# stm32_nrf.net
KiCad netlist of a schematic drawn in EAGLE
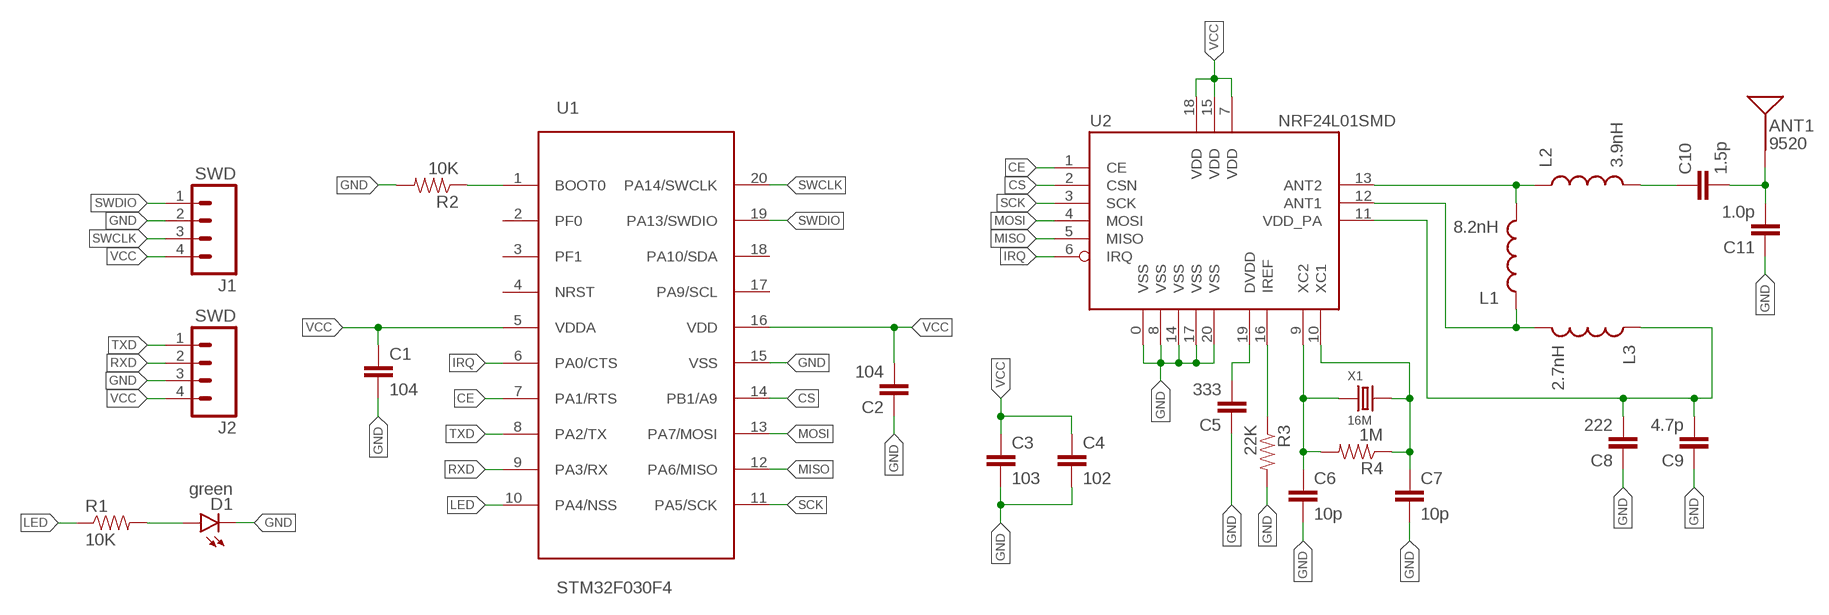
[diagram p0: schematic, sheet 1]

(export (version "E")
  (design (tool "Eeschema 10.0.6"))
  (components
    (comp (ref "ANT1")
      (value "9520")
      (footprint "eagle-import:ANT-2.4GHZ-9.5X2.0MM")
      (libsource (lib "eagle-import") (part "ANTENNA2.4GHZ-9.5X2.0MM"))
    )
    (comp (ref "C1")
      (value "104")
      (footprint "eagle-import:0402-CAP")
      (libsource (lib "eagle-import") (part "CAP0402-CAP"))
    )
    (comp (ref "C2")
      (value "104")
      (footprint "eagle-import:0402-CAP")
      (libsource (lib "eagle-import") (part "CAP0402-CAP"))
    )
    (comp (ref "C3")
      (value "103")
      (footprint "eagle-import:0402-CAP")
      (libsource (lib "eagle-import") (part "CAP0402-CAP"))
    )
    (comp (ref "C4")
      (value "102")
      (footprint "eagle-import:0402-CAP")
      (libsource (lib "eagle-import") (part "CAP0402-CAP"))
    )
    (comp (ref "C5")
      (value "333")
      (footprint "eagle-import:0402-CAP")
      (libsource (lib "eagle-import") (part "CAP0402-CAP"))
    )
    (comp (ref "C6")
      (value "10p")
      (footprint "eagle-import:0402-CAP")
      (libsource (lib "eagle-import") (part "CAP0402-CAP"))
    )
    (comp (ref "C7")
      (value "10p")
      (footprint "eagle-import:0402-CAP")
      (libsource (lib "eagle-import") (part "CAP0402-CAP"))
    )
    (comp (ref "C8")
      (value "222")
      (footprint "eagle-import:0402-CAP")
      (libsource (lib "eagle-import") (part "CAP0402-CAP"))
    )
    (comp (ref "C9")
      (value "4.7p")
      (footprint "eagle-import:0402-CAP")
      (libsource (lib "eagle-import") (part "CAP0402-CAP"))
    )
    (comp (ref "C10")
      (value "1.5p")
      (footprint "eagle-import:0402-CAP")
      (libsource (lib "eagle-import") (part "CAP0402-CAP"))
    )
    (comp (ref "C11")
      (value "1.0p")
      (footprint "eagle-import:0402-CAP")
      (libsource (lib "eagle-import") (part "CAP0402-CAP"))
    )
    (comp (ref "D1")
      (value "green")
      (footprint "eagle-import:LED-0603-EASY")
      (libsource (lib "eagle-import") (part "LED-EASY"))
    )
    (comp (ref "J1")
      (value "SWD")
      (footprint "eagle-import:1X04_NO_SILK")
      (libsource (lib "eagle-import") (part "M041X04_NO_SILK"))
    )
    (comp (ref "J2")
      (value "SWD")
      (footprint "eagle-import:1X04_NO_SILK")
      (libsource (lib "eagle-import") (part "M041X04_NO_SILK"))
    )
    (comp (ref "L1")
      (value "8.2nH")
      (footprint "eagle-import:C0402")
      (libsource (lib "eagle-import") (part "INDUCTOR0402"))
    )
    (comp (ref "L2")
      (value "3.9nH")
      (footprint "eagle-import:C0402")
      (libsource (lib "eagle-import") (part "INDUCTOR0402"))
    )
    (comp (ref "L3")
      (value "2.7nH")
      (footprint "eagle-import:C0402")
      (libsource (lib "eagle-import") (part "INDUCTOR0402"))
    )
    (comp (ref "R1")
      (value "10K")
      (footprint "eagle-import:0402-RES")
      (libsource (lib "eagle-import") (part "RESISTOR0402"))
    )
    (comp (ref "R2")
      (value "10K")
      (footprint "eagle-import:0402-RES")
      (libsource (lib "eagle-import") (part "RESISTOR0402"))
    )
    (comp (ref "R3")
      (value "22K")
      (footprint "eagle-import:0402-RES")
      (libsource (lib "eagle-import") (part "RESISTOR0402"))
    )
    (comp (ref "R4")
      (value "1M")
      (footprint "eagle-import:0402-RES")
      (libsource (lib "eagle-import") (part "RESISTOR0402"))
    )
    (comp (ref "U1")
      (value "STM32F030F4")
      (footprint "eagle-import:TSSOP20")
      (libsource (lib "eagle-import") (part "STM32F030F4"))
    )
    (comp (ref "U2")
      (value "NRF24L01SMD")
      (footprint "eagle-import:QFN20")
      (libsource (lib "eagle-import") (part "NRF24L01SMD"))
    )
    (comp (ref "X1")
      (value "16M")
      (footprint "eagle-import:X4-SMD-3.2X2.5X0.7MM")
      (libsource (lib "eagle-import") (part "CRYSTAL'3225'"))
    )
  )
  (nets
    (net (code "1") (name "CE") (class "Default")
      (node (ref "U1") (pin "7") (pinfunction "PA1/RTS_7") (pintype "bidirectional"))
      (node (ref "U2") (pin "1") (pinfunction "CE_1") (pintype "input"))
    )
    (net (code "2") (name "CS") (class "Default")
      (node (ref "U1") (pin "14") (pinfunction "PB1/A9_14") (pintype "bidirectional"))
      (node (ref "U2") (pin "2") (pinfunction "CSN_2") (pintype "input"))
    )
    (net (code "3") (name "GND") (class "Default")
      (node (ref "C1") (pin "2") (pinfunction "2_2") (pintype "passive"))
      (node (ref "C11") (pin "1") (pinfunction "1_1") (pintype "passive"))
      (node (ref "C2") (pin "1") (pinfunction "1_1") (pintype "passive"))
      (node (ref "C3") (pin "2") (pinfunction "2_2") (pintype "passive"))
      (node (ref "C4") (pin "2") (pinfunction "2_2") (pintype "passive"))
      (node (ref "C5") (pin "1") (pinfunction "1_1") (pintype "passive"))
      (node (ref "C6") (pin "2") (pinfunction "2_2") (pintype "passive"))
      (node (ref "C7") (pin "2") (pinfunction "2_2") (pintype "passive"))
      (node (ref "C8") (pin "1") (pinfunction "1_1") (pintype "passive"))
      (node (ref "C9") (pin "1") (pinfunction "1_1") (pintype "passive"))
      (node (ref "D1") (pin "-") (pinfunction "C_-") (pintype "passive"))
      (node (ref "J1") (pin "2") (pinfunction "2_2") (pintype "passive"))
      (node (ref "J2") (pin "3") (pinfunction "3_3") (pintype "passive"))
      (node (ref "R2") (pin "2") (pinfunction "2_2") (pintype "passive"))
      (node (ref "R3") (pin "2") (pinfunction "2_2") (pintype "passive"))
      (node (ref "U1") (pin "15") (pinfunction "VSS_15") (pintype "bidirectional"))
      (node (ref "U2") (pin "0") (pinfunction "VSS_0") (pintype "power_in"))
      (node (ref "U2") (pin "14") (pinfunction "VSS_14") (pintype "power_in"))
      (node (ref "U2") (pin "17") (pinfunction "VSS_17") (pintype "power_in"))
      (node (ref "U2") (pin "20") (pinfunction "VSS_20") (pintype "power_in"))
      (node (ref "U2") (pin "8") (pinfunction "VSS_8") (pintype "power_in"))
    )
    (net (code "4") (name "IRQ") (class "Default")
      (node (ref "U1") (pin "6") (pinfunction "PA0/CTS_6") (pintype "bidirectional"))
      (node (ref "U2") (pin "6") (pinfunction "IRQ_6") (pintype "output"))
    )
    (net (code "5") (name "LED") (class "Default")
      (node (ref "R1") (pin "1") (pinfunction "1_1") (pintype "passive"))
      (node (ref "U1") (pin "10") (pinfunction "PA4/NSS_10") (pintype "bidirectional"))
    )
    (net (code "6") (name "MISO") (class "Default")
      (node (ref "U1") (pin "12") (pinfunction "PA6/MISO_12") (pintype "bidirectional"))
      (node (ref "U2") (pin "5") (pinfunction "MISO_5") (pintype "output"))
    )
    (net (code "7") (name "MOSI") (class "Default")
      (node (ref "U1") (pin "13") (pinfunction "PA7/MOSI_13") (pintype "bidirectional"))
      (node (ref "U2") (pin "4") (pinfunction "MOSI_4") (pintype "input"))
    )
    (net (code "8") (name "Net-(ANT1-SIGNAL)") (class "Default")
      (node (ref "ANT1") (pin "FEED") (pinfunction "SIGNAL_FEED") (pintype "bidirectional"))
      (node (ref "C10") (pin "2") (pinfunction "2_2") (pintype "passive"))
      (node (ref "C11") (pin "2") (pinfunction "2_2") (pintype "passive"))
    )
    (net (code "9") (name "Net-(C10-Pad1)") (class "Default")
      (node (ref "C10") (pin "1") (pinfunction "1_1") (pintype "passive"))
      (node (ref "L2") (pin "2") (pinfunction "2_2") (pintype "passive"))
    )
    (net (code "10") (name "Net-(D1-A)") (class "Default")
      (node (ref "D1") (pin "+") (pinfunction "A_+") (pintype "passive"))
      (node (ref "R1") (pin "2") (pinfunction "2_2") (pintype "passive"))
    )
    (net (code "11") (name "Net-(U1-BOOT0)") (class "Default")
      (node (ref "R2") (pin "1") (pinfunction "1_1") (pintype "passive"))
      (node (ref "U1") (pin "1") (pinfunction "BOOT0_1") (pintype "bidirectional"))
    )
    (net (code "12") (name "Net-(U2-ANT1)") (class "Default")
      (node (ref "L1") (pin "1") (pinfunction "1_1") (pintype "passive"))
      (node (ref "L3") (pin "2") (pinfunction "2_2") (pintype "passive"))
      (node (ref "U2") (pin "12") (pinfunction "ANT1_12") (pintype "output"))
    )
    (net (code "13") (name "Net-(U2-ANT2)") (class "Default")
      (node (ref "L1") (pin "2") (pinfunction "2_2") (pintype "passive"))
      (node (ref "L2") (pin "1") (pinfunction "1_1") (pintype "passive"))
      (node (ref "U2") (pin "13") (pinfunction "ANT2_13") (pintype "output"))
    )
    (net (code "14") (name "Net-(U2-DVDD)") (class "Default")
      (node (ref "C5") (pin "2") (pinfunction "2_2") (pintype "passive"))
      (node (ref "U2") (pin "19") (pinfunction "DVDD_19") (pintype "power_in"))
    )
    (net (code "15") (name "Net-(U2-IREF)") (class "Default")
      (node (ref "R3") (pin "1") (pinfunction "1_1") (pintype "passive"))
      (node (ref "U2") (pin "16") (pinfunction "IREF_16") (pintype "input"))
    )
    (net (code "16") (name "Net-(U2-VDD_PA)") (class "Default")
      (node (ref "C8") (pin "2") (pinfunction "2_2") (pintype "passive"))
      (node (ref "C9") (pin "2") (pinfunction "2_2") (pintype "passive"))
      (node (ref "L3") (pin "1") (pinfunction "1_1") (pintype "passive"))
      (node (ref "U2") (pin "11") (pinfunction "VDD_PA_11") (pintype "power_in"))
    )
    (net (code "17") (name "Net-(U2-XC1)") (class "Default")
      (node (ref "C7") (pin "1") (pinfunction "1_1") (pintype "passive"))
      (node (ref "R4") (pin "1") (pinfunction "1_1") (pintype "passive"))
      (node (ref "U2") (pin "10") (pinfunction "XC1_10") (pintype "input"))
      (node (ref "X1") (pin "3") (pinfunction "2_3") (pintype "passive"))
    )
    (net (code "18") (name "Net-(U2-XC2)") (class "Default")
      (node (ref "C6") (pin "1") (pinfunction "1_1") (pintype "passive"))
      (node (ref "R4") (pin "2") (pinfunction "2_2") (pintype "passive"))
      (node (ref "U2") (pin "9") (pinfunction "XC2_9") (pintype "input"))
      (node (ref "X1") (pin "1") (pinfunction "1_1") (pintype "passive"))
    )
    (net (code "19") (name "RXD") (class "Default")
      (node (ref "J2") (pin "2") (pinfunction "2_2") (pintype "passive"))
      (node (ref "U1") (pin "9") (pinfunction "PA3/RX_9") (pintype "bidirectional"))
    )
    (net (code "20") (name "SCK") (class "Default")
      (node (ref "U1") (pin "11") (pinfunction "PA5/SCK_11") (pintype "bidirectional"))
      (node (ref "U2") (pin "3") (pinfunction "SCK_3") (pintype "input"))
    )
    (net (code "21") (name "SWCLK") (class "Default")
      (node (ref "J1") (pin "3") (pinfunction "3_3") (pintype "passive"))
      (node (ref "U1") (pin "20") (pinfunction "PA14/SWCLK_20") (pintype "bidirectional"))
    )
    (net (code "22") (name "SWDIO") (class "Default")
      (node (ref "J1") (pin "1") (pinfunction "1_1") (pintype "passive"))
      (node (ref "U1") (pin "19") (pinfunction "PA13/SWDIO_19") (pintype "bidirectional"))
    )
    (net (code "23") (name "TXD") (class "Default")
      (node (ref "J2") (pin "1") (pinfunction "1_1") (pintype "passive"))
      (node (ref "U1") (pin "8") (pinfunction "PA2/TX_8") (pintype "bidirectional"))
    )
    (net (code "24") (name "VCC") (class "Default")
      (node (ref "C1") (pin "1") (pinfunction "1_1") (pintype "passive"))
      (node (ref "C2") (pin "2") (pinfunction "2_2") (pintype "passive"))
      (node (ref "C3") (pin "1") (pinfunction "1_1") (pintype "passive"))
      (node (ref "C4") (pin "1") (pinfunction "1_1") (pintype "passive"))
      (node (ref "J1") (pin "4") (pinfunction "4_4") (pintype "passive"))
      (node (ref "J2") (pin "4") (pinfunction "4_4") (pintype "passive"))
      (node (ref "U1") (pin "16") (pinfunction "VDD_16") (pintype "bidirectional"))
      (node (ref "U1") (pin "5") (pinfunction "VDDA_5") (pintype "bidirectional"))
      (node (ref "U2") (pin "15") (pinfunction "VDD_15") (pintype "power_in"))
      (node (ref "U2") (pin "18") (pinfunction "VDD_18") (pintype "power_in"))
      (node (ref "U2") (pin "7") (pinfunction "VDD_7") (pintype "power_in"))
    )
    (net (code "25") (name "unconnected-(U1-NRST-Pad4)") (class "Default")
      (node (ref "U1") (pin "4") (pinfunction "NRST_4") (pintype "bidirectional"))
    )
    (net (code "26") (name "unconnected-(U1-PA9{slash}SCL-Pad17)") (class "Default")
      (node (ref "U1") (pin "17") (pinfunction "PA9/SCL_17") (pintype "bidirectional"))
    )
    (net (code "27") (name "unconnected-(U1-PA10{slash}SDA-Pad18)") (class "Default")
      (node (ref "U1") (pin "18") (pinfunction "PA10/SDA_18") (pintype "bidirectional"))
    )
    (net (code "28") (name "unconnected-(U1-PF0-Pad2)") (class "Default")
      (node (ref "U1") (pin "2") (pinfunction "PF0_2") (pintype "bidirectional"))
    )
    (net (code "29") (name "unconnected-(U1-PF1-Pad3)") (class "Default")
      (node (ref "U1") (pin "3") (pinfunction "PF1_3") (pintype "bidirectional"))
    )
  )
)
